# LOFM.net
KiCad netlist of a schematic drawn in EAGLE
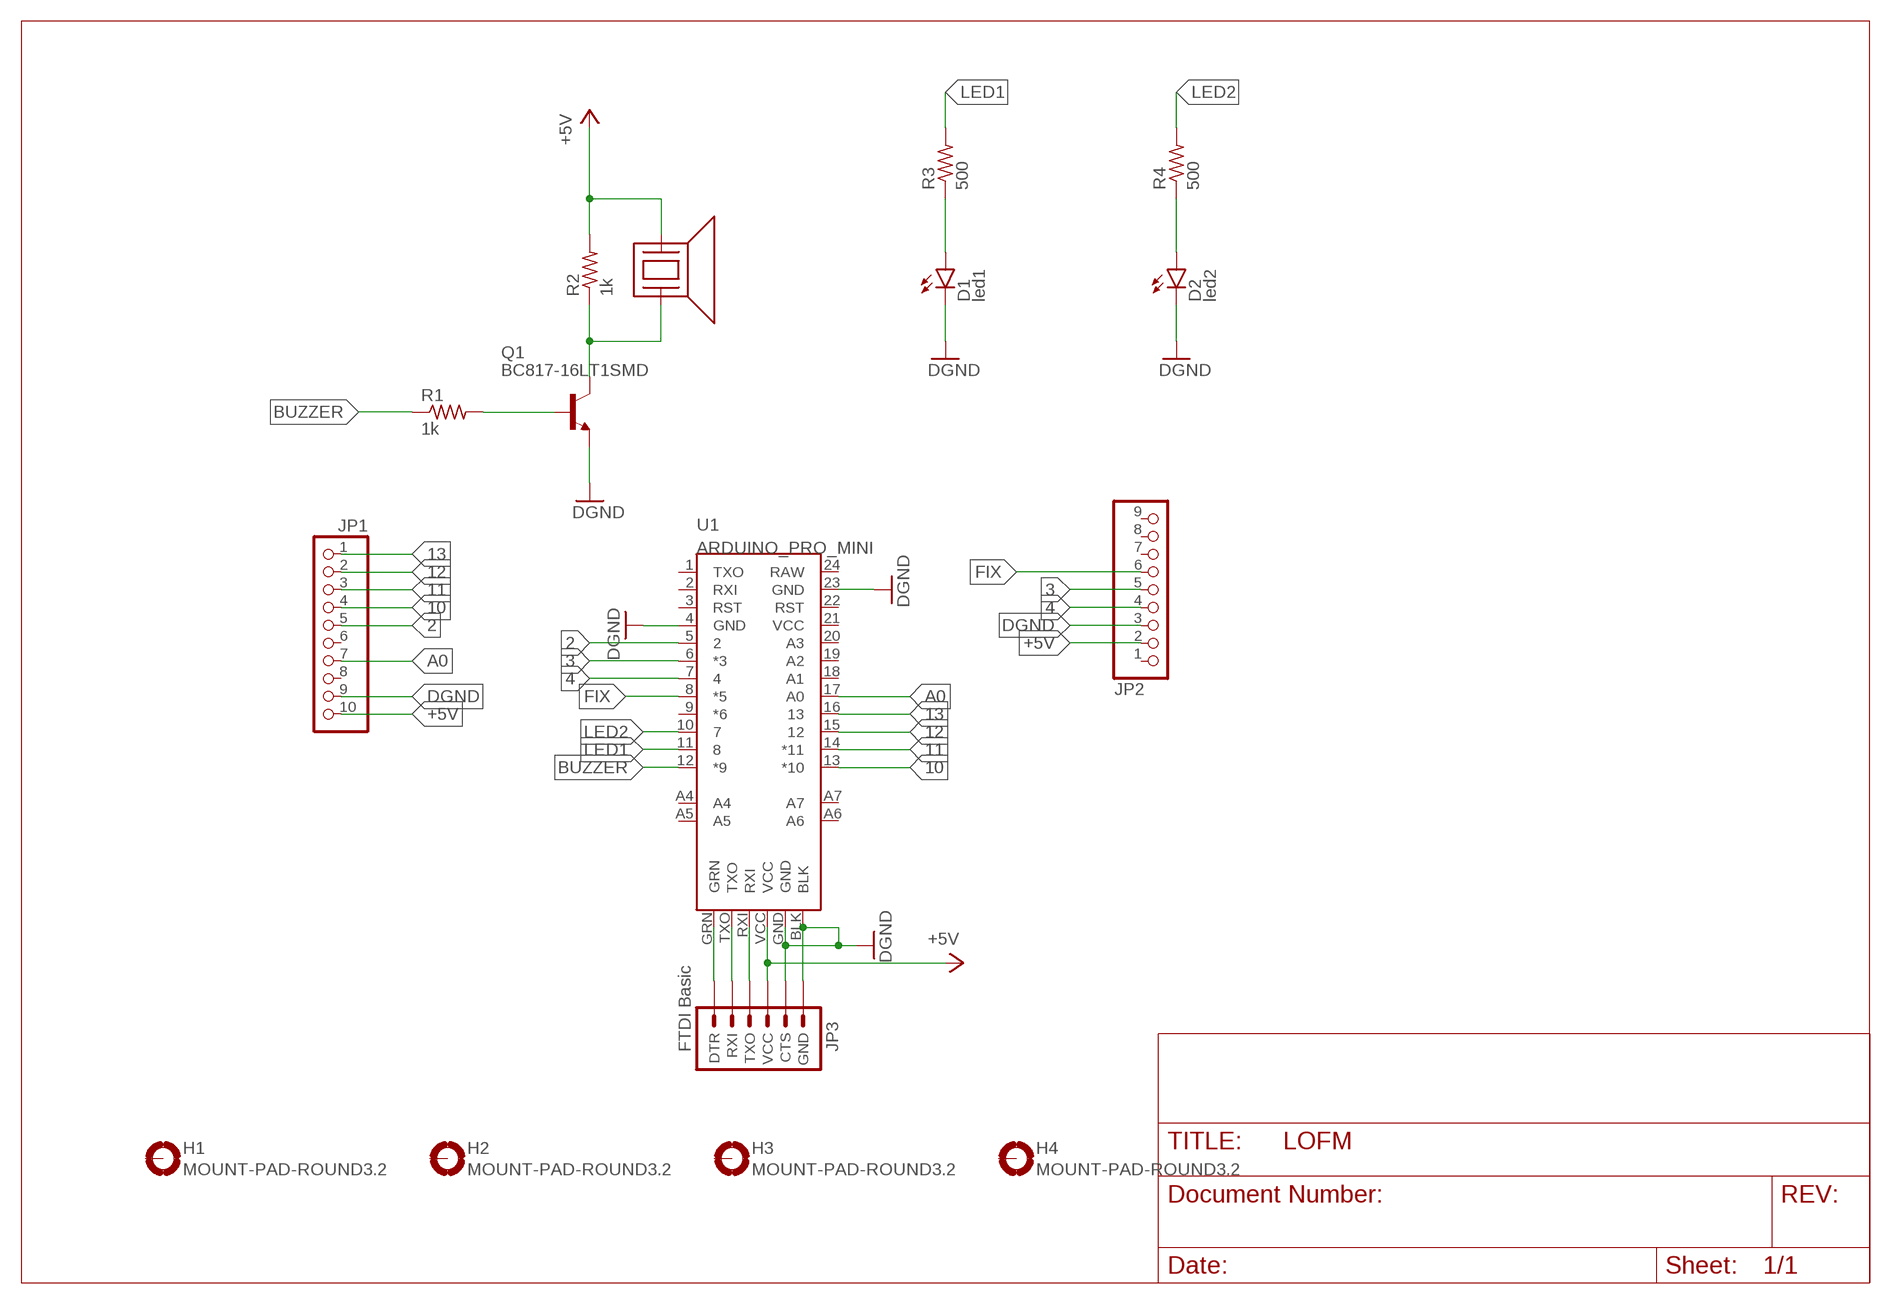
[diagram p0: schematic, sheet 1]

(export (version "E")
  (design (tool "Eeschema 10.0.6"))
  (components
    (comp (ref "D1")
      (value "led1")
      (footprint "eagle-import:LED3MM")
      (libsource (lib "eagle-import") (part "LED3MM"))
    )
    (comp (ref "D2")
      (value "led2")
      (footprint "eagle-import:LED3MM")
      (libsource (lib "eagle-import") (part "LED3MM"))
    )
    (comp (ref "H1")
      (value "MOUNT-PAD-ROUND3.2")
      (footprint "eagle-import:3,2-PAD")
      (libsource (lib "eagle-import") (part "MOUNT-PAD-ROUND3.2"))
    )
    (comp (ref "H2")
      (value "MOUNT-PAD-ROUND3.2")
      (footprint "eagle-import:3,2-PAD")
      (libsource (lib "eagle-import") (part "MOUNT-PAD-ROUND3.2"))
    )
    (comp (ref "H3")
      (value "MOUNT-PAD-ROUND3.2")
      (footprint "eagle-import:3,2-PAD")
      (libsource (lib "eagle-import") (part "MOUNT-PAD-ROUND3.2"))
    )
    (comp (ref "H4")
      (value "MOUNT-PAD-ROUND3.2")
      (footprint "eagle-import:3,2-PAD")
      (libsource (lib "eagle-import") (part "MOUNT-PAD-ROUND3.2"))
    )
    (comp (ref "JP1")
      (value "HEADER-1X1070MIL")
      (footprint "eagle-import:1X10_ROUND70")
      (libsource (lib "eagle-import") (part "HEADER-1X1070MIL"))
    )
    (comp (ref "JP2")
      (value "HEADER-1X970MIL")
      (footprint "eagle-import:1X09_ROUND_70")
      (libsource (lib "eagle-import") (part "HEADER-1X970MIL"))
    )
    (comp (ref "JP3")
      (value "FTDI Basic")
      (footprint "eagle-import:1X06")
      (libsource (lib "eagle-import") (part "ARDUINO_SERIAL_PROGRAMPTH"))
    )
    (comp (ref "Q1")
      (value "BC817-16LT1SMD")
      (footprint "eagle-import:SOT23-BEC")
      (libsource (lib "eagle-import") (part "BC817SMD-16LT1"))
    )
    (comp (ref "R1")
      (value "1k")
      (footprint "eagle-import:R0603(1608)")
      (libsource (lib "eagle-import") (part "R0603(1608)"))
    )
    (comp (ref "R2")
      (value "1k")
      (footprint "eagle-import:R0603(1608)")
      (libsource (lib "eagle-import") (part "R0603(1608)"))
    )
    (comp (ref "R3")
      (value "500")
      (footprint "eagle-import:R0603(1608)")
      (libsource (lib "eagle-import") (part "R0603(1608)"))
    )
    (comp (ref "R4")
      (value "500")
      (footprint "eagle-import:R0603(1608)")
      (libsource (lib "eagle-import") (part "R0603(1608)"))
    )
    (comp (ref "U1")
      (value "ARDUINO_PRO_MINI")
      (footprint "eagle-import:ARDUINO_PRO_MINI")
      (libsource (lib "eagle-import") (part "ARDUINO_PRO_MINI"))
    )
    (comp (ref "U7")
      (value "BUZZER")
      (footprint "eagle-import:PS1240")
      (libsource (lib "eagle-import") (part "BUZZER"))
    )
  )
  (nets
    (net (code "1") (name "+5V") (class "Default")
      (node (ref "JP1") (pin "10") (pinfunction "10_10") (pintype "passive"))
      (node (ref "JP2") (pin "2") (pinfunction "2_2") (pintype "passive"))
      (node (ref "JP3") (pin "4") (pinfunction "VCC_4") (pintype "passive"))
      (node (ref "R2") (pin "2") (pinfunction "2_2") (pintype "passive"))
      (node (ref "U1") (pin "VCC") (pinfunction "VCC_VCC") (pintype "bidirectional"))
      (node (ref "U7") (pin "1") (pinfunction "P$1_1") (pintype "bidirectional"))
    )
    (net (code "2") (name "2") (class "Default")
      (node (ref "JP1") (pin "5") (pinfunction "5_5") (pintype "passive"))
      (node (ref "U1") (pin "5") (pinfunction "2_5") (pintype "bidirectional"))
    )
    (net (code "3") (name "3") (class "Default")
      (node (ref "JP2") (pin "5") (pinfunction "5_5") (pintype "passive"))
      (node (ref "U1") (pin "6") (pinfunction "*3_6") (pintype "bidirectional"))
    )
    (net (code "4") (name "4") (class "Default")
      (node (ref "JP2") (pin "4") (pinfunction "4_4") (pintype "passive"))
      (node (ref "U1") (pin "7") (pinfunction "4_7") (pintype "bidirectional"))
    )
    (net (code "5") (name "10") (class "Default")
      (node (ref "JP1") (pin "4") (pinfunction "4_4") (pintype "passive"))
      (node (ref "U1") (pin "13") (pinfunction "*10_13") (pintype "bidirectional"))
    )
    (net (code "6") (name "11") (class "Default")
      (node (ref "JP1") (pin "3") (pinfunction "3_3") (pintype "passive"))
      (node (ref "U1") (pin "14") (pinfunction "*11_14") (pintype "bidirectional"))
    )
    (net (code "7") (name "12") (class "Default")
      (node (ref "JP1") (pin "2") (pinfunction "2_2") (pintype "passive"))
      (node (ref "U1") (pin "15") (pinfunction "12_15") (pintype "bidirectional"))
    )
    (net (code "8") (name "13") (class "Default")
      (node (ref "JP1") (pin "1") (pinfunction "1_1") (pintype "passive"))
      (node (ref "U1") (pin "16") (pinfunction "13_16") (pintype "bidirectional"))
    )
    (net (code "9") (name "A0") (class "Default")
      (node (ref "JP1") (pin "7") (pinfunction "7_7") (pintype "passive"))
      (node (ref "U1") (pin "17") (pinfunction "A0_17") (pintype "bidirectional"))
    )
    (net (code "10") (name "BUZZER") (class "Default")
      (node (ref "R1") (pin "1") (pinfunction "1_1") (pintype "passive"))
      (node (ref "U1") (pin "12") (pinfunction "*9_12") (pintype "bidirectional"))
    )
    (net (code "11") (name "DGND") (class "Default")
      (node (ref "D1") (pin "K") (pinfunction "C_K") (pintype "passive"))
      (node (ref "D2") (pin "K") (pinfunction "C_K") (pintype "passive"))
      (node (ref "JP1") (pin "9") (pinfunction "9_9") (pintype "passive"))
      (node (ref "JP2") (pin "3") (pinfunction "3_3") (pintype "passive"))
      (node (ref "JP3") (pin "5") (pinfunction "CTS_5") (pintype "passive"))
      (node (ref "JP3") (pin "6") (pinfunction "GND_6") (pintype "passive"))
      (node (ref "Q1") (pin "E") (pinfunction "E_E") (pintype "passive"))
      (node (ref "U1") (pin "23") (pinfunction "GND_23") (pintype "bidirectional"))
      (node (ref "U1") (pin "4") (pinfunction "GND_4") (pintype "bidirectional"))
      (node (ref "U1") (pin "BLK") (pinfunction "BLK_BLK") (pintype "bidirectional"))
      (node (ref "U1") (pin "GND") (pinfunction "GND_GND") (pintype "bidirectional"))
    )
    (net (code "12") (name "FIX") (class "Default")
      (node (ref "JP2") (pin "6") (pinfunction "6_6") (pintype "passive"))
      (node (ref "U1") (pin "8") (pinfunction "*5_8") (pintype "bidirectional"))
    )
    (net (code "13") (name "LED1") (class "Default")
      (node (ref "R3") (pin "2") (pinfunction "2_2") (pintype "passive"))
      (node (ref "U1") (pin "11") (pinfunction "8_11") (pintype "bidirectional"))
    )
    (net (code "14") (name "LED2") (class "Default")
      (node (ref "R4") (pin "2") (pinfunction "2_2") (pintype "passive"))
      (node (ref "U1") (pin "10") (pinfunction "7_10") (pintype "bidirectional"))
    )
    (net (code "15") (name "Net-(D1-PadA)") (class "Default")
      (node (ref "D1") (pin "A") (pinfunction "A_A") (pintype "passive"))
      (node (ref "R3") (pin "1") (pinfunction "1_1") (pintype "passive"))
    )
    (net (code "16") (name "Net-(D2-PadA)") (class "Default")
      (node (ref "D2") (pin "A") (pinfunction "A_A") (pintype "passive"))
      (node (ref "R4") (pin "1") (pinfunction "1_1") (pintype "passive"))
    )
    (net (code "17") (name "Net-(JP3-DTR)") (class "Default")
      (node (ref "JP3") (pin "1") (pinfunction "DTR_1") (pintype "passive"))
      (node (ref "U1") (pin "GRN") (pinfunction "GRN_GRN") (pintype "bidirectional"))
    )
    (net (code "18") (name "Net-(JP3-RXI)") (class "Default")
      (node (ref "JP3") (pin "2") (pinfunction "RXI_2") (pintype "passive"))
      (node (ref "U1") (pin "TXO") (pinfunction "TXO_TXO") (pintype "bidirectional"))
    )
    (net (code "19") (name "Net-(JP3-TXO)") (class "Default")
      (node (ref "JP3") (pin "3") (pinfunction "TXO_3") (pintype "passive"))
      (node (ref "U1") (pin "RXI") (pinfunction "RXI_RXI") (pintype "bidirectional"))
    )
    (net (code "20") (name "Net-(Q1-PadB)") (class "Default")
      (node (ref "Q1") (pin "B") (pinfunction "B_B") (pintype "passive"))
      (node (ref "R1") (pin "2") (pinfunction "2_2") (pintype "passive"))
    )
    (net (code "21") (name "Net-(U7-P$2)") (class "Default")
      (node (ref "Q1") (pin "C") (pinfunction "C_C") (pintype "passive"))
      (node (ref "R2") (pin "1") (pinfunction "1_1") (pintype "passive"))
      (node (ref "U7") (pin "2") (pinfunction "P$2_2") (pintype "bidirectional"))
    )
    (net (code "22") (name "unconnected-(H1-MOUNT-PadB3,2)") (class "Default")
      (node (ref "H1") (pin "B3,2") (pinfunction "MOUNT_B3,2") (pintype "passive"))
    )
    (net (code "23") (name "unconnected-(H2-MOUNT-PadB3,2)") (class "Default")
      (node (ref "H2") (pin "B3,2") (pinfunction "MOUNT_B3,2") (pintype "passive"))
    )
    (net (code "24") (name "unconnected-(H3-MOUNT-PadB3,2)") (class "Default")
      (node (ref "H3") (pin "B3,2") (pinfunction "MOUNT_B3,2") (pintype "passive"))
    )
    (net (code "25") (name "unconnected-(H4-MOUNT-PadB3,2)") (class "Default")
      (node (ref "H4") (pin "B3,2") (pinfunction "MOUNT_B3,2") (pintype "passive"))
    )
    (net (code "26") (name "unconnected-(JP1-Pad6)") (class "Default")
      (node (ref "JP1") (pin "6") (pinfunction "6_6") (pintype "passive"))
    )
    (net (code "27") (name "unconnected-(JP1-Pad8)") (class "Default")
      (node (ref "JP1") (pin "8") (pinfunction "8_8") (pintype "passive"))
    )
    (net (code "28") (name "unconnected-(JP2-Pad1)") (class "Default")
      (node (ref "JP2") (pin "1") (pinfunction "1_1") (pintype "passive"))
    )
    (net (code "29") (name "unconnected-(JP2-Pad7)") (class "Default")
      (node (ref "JP2") (pin "7") (pinfunction "7_7") (pintype "passive"))
    )
    (net (code "30") (name "unconnected-(JP2-Pad8)") (class "Default")
      (node (ref "JP2") (pin "8") (pinfunction "8_8") (pintype "passive"))
    )
    (net (code "31") (name "unconnected-(JP2-Pad9)") (class "Default")
      (node (ref "JP2") (pin "9") (pinfunction "9_9") (pintype "passive"))
    )
    (net (code "32") (name "unconnected-(U1-*6-Pad9)") (class "Default")
      (node (ref "U1") (pin "9") (pinfunction "*6_9") (pintype "bidirectional"))
    )
    (net (code "33") (name "unconnected-(U1-A1-Pad18)") (class "Default")
      (node (ref "U1") (pin "18") (pinfunction "A1_18") (pintype "bidirectional"))
    )
    (net (code "34") (name "unconnected-(U1-A2-Pad19)") (class "Default")
      (node (ref "U1") (pin "19") (pinfunction "A2_19") (pintype "bidirectional"))
    )
    (net (code "35") (name "unconnected-(U1-A3-Pad20)") (class "Default")
      (node (ref "U1") (pin "20") (pinfunction "A3_20") (pintype "bidirectional"))
    )
    (net (code "36") (name "unconnected-(U1-PadA4)") (class "Default")
      (node (ref "U1") (pin "A4") (pinfunction "A4_A4") (pintype "bidirectional"))
    )
    (net (code "37") (name "unconnected-(U1-PadA5)") (class "Default")
      (node (ref "U1") (pin "A5") (pinfunction "A5_A5") (pintype "bidirectional"))
    )
    (net (code "38") (name "unconnected-(U1-PadA6)") (class "Default")
      (node (ref "U1") (pin "A6") (pinfunction "A6_A6") (pintype "bidirectional"))
    )
    (net (code "39") (name "unconnected-(U1-PadA7)") (class "Default")
      (node (ref "U1") (pin "A7") (pinfunction "A7_A7") (pintype "bidirectional"))
    )
    (net (code "40") (name "unconnected-(U1-RAW-Pad24)") (class "Default")
      (node (ref "U1") (pin "24") (pinfunction "RAW_24") (pintype "bidirectional"))
    )
    (net (code "41") (name "unconnected-(U1-RST-Pad3)") (class "Default")
      (node (ref "U1") (pin "3") (pinfunction "RST_3") (pintype "bidirectional"))
    )
    (net (code "42") (name "unconnected-(U1-RST-Pad22)") (class "Default")
      (node (ref "U1") (pin "22") (pinfunction "RST_22") (pintype "bidirectional"))
    )
    (net (code "43") (name "unconnected-(U1-RXI-Pad2)") (class "Default")
      (node (ref "U1") (pin "2") (pinfunction "RXI_2") (pintype "bidirectional"))
    )
    (net (code "44") (name "unconnected-(U1-TXO-Pad1)") (class "Default")
      (node (ref "U1") (pin "1") (pinfunction "TXO_1") (pintype "bidirectional"))
    )
    (net (code "45") (name "unconnected-(U1-VCC-Pad21)") (class "Default")
      (node (ref "U1") (pin "21") (pinfunction "VCC_21") (pintype "bidirectional"))
    )
  )
)
